# axiom_beta_plugin_module_3xPMOD_v1_2_r1_.net
KiCad netlist of a schematic drawn in EAGLE
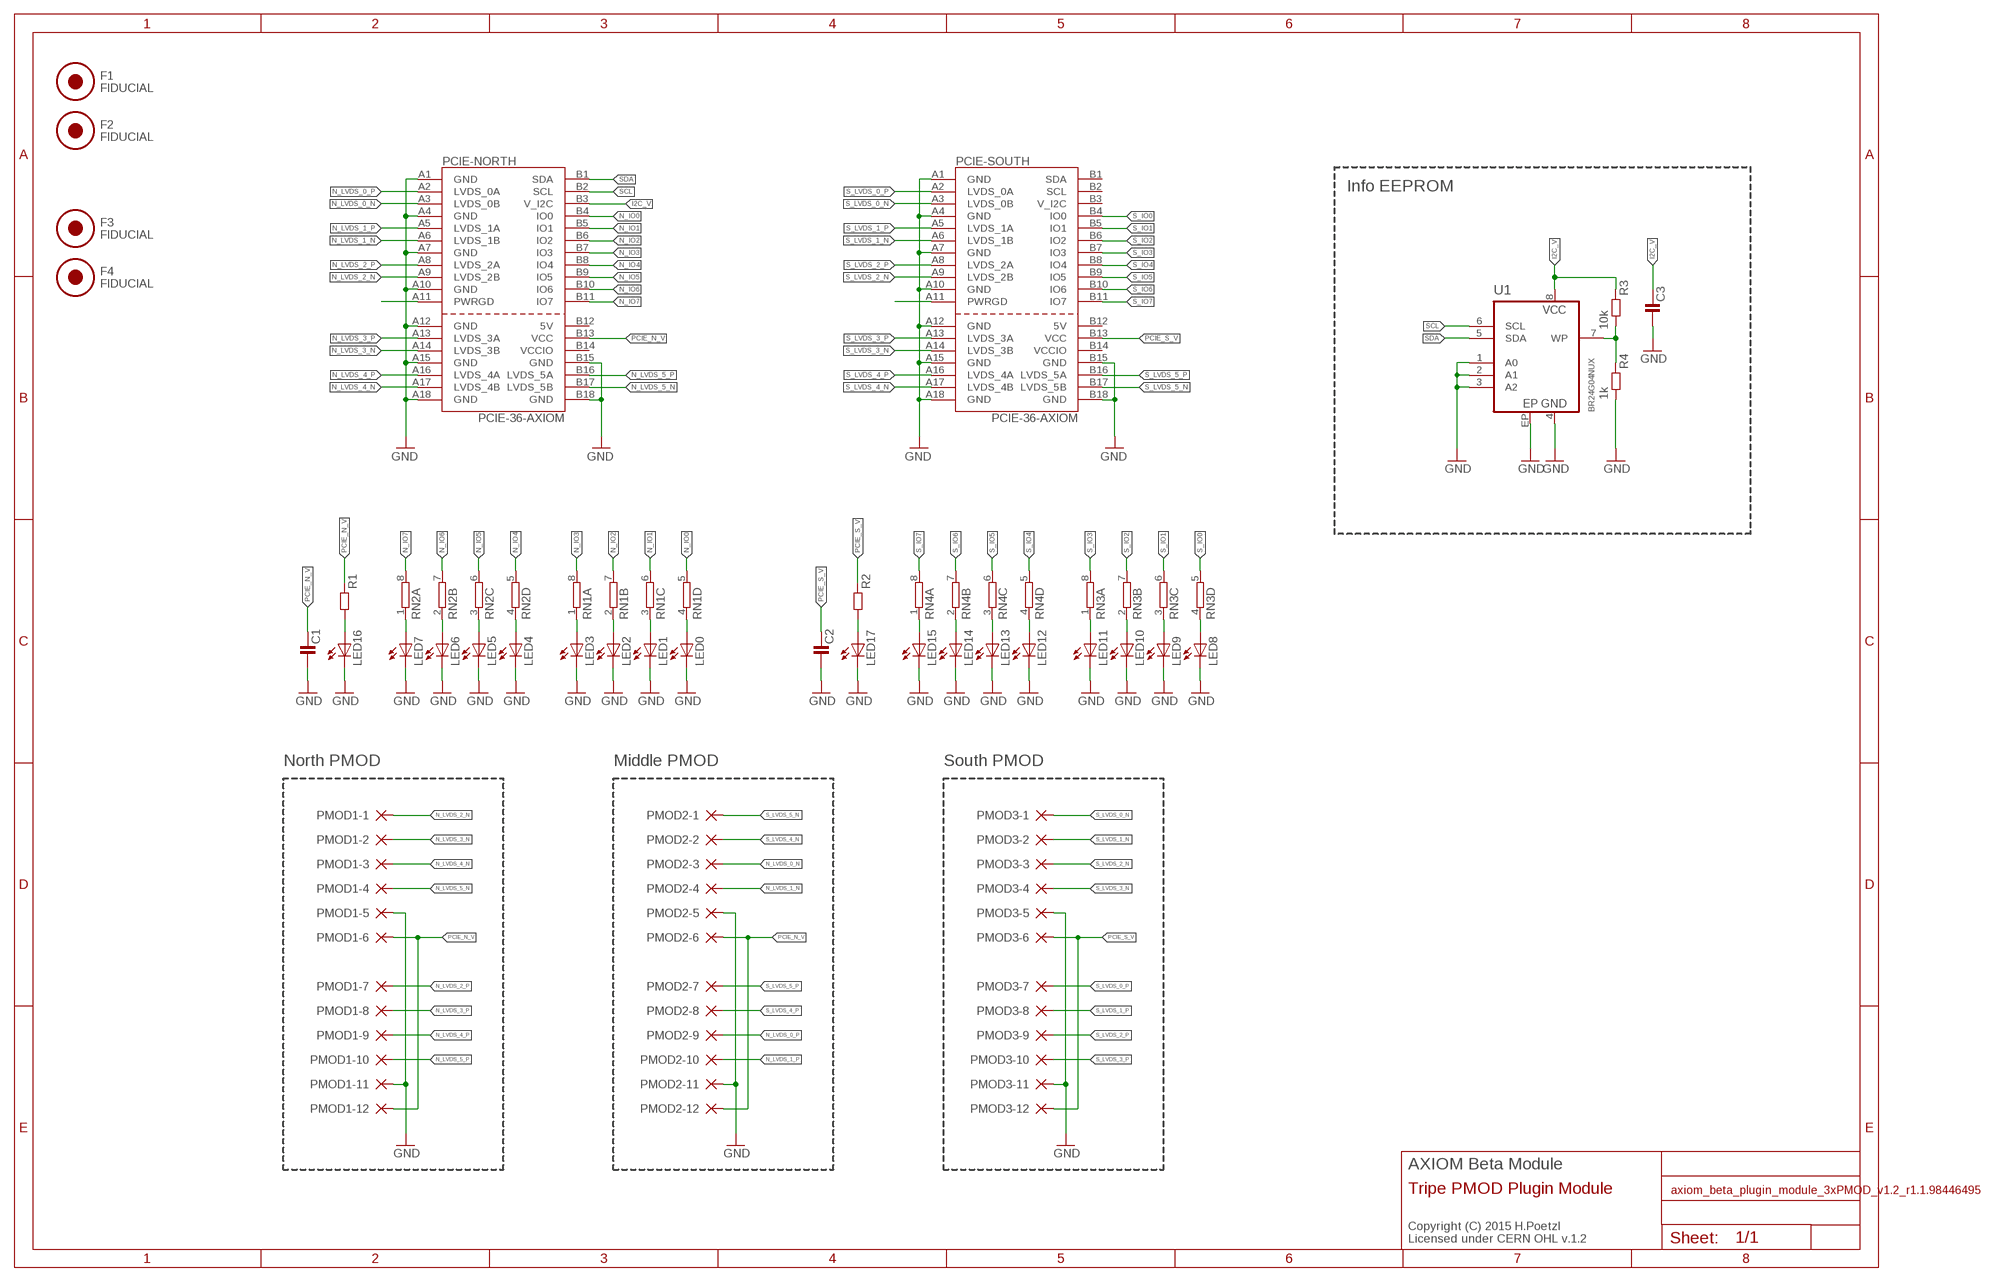
[diagram p0: schematic, sheet 1]

(export (version "E")
  (design (tool "Eeschema 10.0.6"))
  (components
    (comp (ref "C1")
      (value "C1206-A")
      (footprint "eagle-import:1206-A")
      (libsource (lib "eagle-import") (part "C1206-A"))
    )
    (comp (ref "C2")
      (value "C1206-A")
      (footprint "eagle-import:1206-A")
      (libsource (lib "eagle-import") (part "C1206-A"))
    )
    (comp (ref "C3")
      (value "C0402-B")
      (footprint "eagle-import:0402-B")
      (libsource (lib "eagle-import") (part "C0402-B"))
    )
    (comp (ref "F1")
      (value "FIDUCIAL")
      (footprint "eagle-import:FID_ARROW")
      (libsource (lib "eagle-import") (part "FIDUCIAL"))
    )
    (comp (ref "F2")
      (value "FIDUCIAL")
      (footprint "eagle-import:FID_ARROW")
      (libsource (lib "eagle-import") (part "FIDUCIAL"))
    )
    (comp (ref "F3")
      (value "FIDUCIAL")
      (footprint "eagle-import:FID_ARROW")
      (libsource (lib "eagle-import") (part "FIDUCIAL"))
    )
    (comp (ref "F4")
      (value "FIDUCIAL")
      (footprint "eagle-import:FID_ARROW")
      (libsource (lib "eagle-import") (part "FIDUCIAL"))
    )
    (comp (ref "LED0")
      (value "LEDCHIPLED_0603")
      (footprint "eagle-import:CHIPLED_0603")
      (libsource (lib "eagle-import") (part "LEDCHIPLED_0603"))
    )
    (comp (ref "LED1")
      (value "LEDCHIPLED_0603")
      (footprint "eagle-import:CHIPLED_0603")
      (libsource (lib "eagle-import") (part "LEDCHIPLED_0603"))
    )
    (comp (ref "LED2")
      (value "LEDCHIPLED_0603")
      (footprint "eagle-import:CHIPLED_0603")
      (libsource (lib "eagle-import") (part "LEDCHIPLED_0603"))
    )
    (comp (ref "LED3")
      (value "LEDCHIPLED_0603")
      (footprint "eagle-import:CHIPLED_0603")
      (libsource (lib "eagle-import") (part "LEDCHIPLED_0603"))
    )
    (comp (ref "LED4")
      (value "LEDCHIPLED_0603")
      (footprint "eagle-import:CHIPLED_0603")
      (libsource (lib "eagle-import") (part "LEDCHIPLED_0603"))
    )
    (comp (ref "LED5")
      (value "LEDCHIPLED_0603")
      (footprint "eagle-import:CHIPLED_0603")
      (libsource (lib "eagle-import") (part "LEDCHIPLED_0603"))
    )
    (comp (ref "LED6")
      (value "LEDCHIPLED_0603")
      (footprint "eagle-import:CHIPLED_0603")
      (libsource (lib "eagle-import") (part "LEDCHIPLED_0603"))
    )
    (comp (ref "LED7")
      (value "LEDCHIPLED_0603")
      (footprint "eagle-import:CHIPLED_0603")
      (libsource (lib "eagle-import") (part "LEDCHIPLED_0603"))
    )
    (comp (ref "LED8")
      (value "LEDCHIPLED_0603")
      (footprint "eagle-import:CHIPLED_0603")
      (libsource (lib "eagle-import") (part "LEDCHIPLED_0603"))
    )
    (comp (ref "LED9")
      (value "LEDCHIPLED_0603")
      (footprint "eagle-import:CHIPLED_0603")
      (libsource (lib "eagle-import") (part "LEDCHIPLED_0603"))
    )
    (comp (ref "LED10")
      (value "LEDCHIPLED_0603")
      (footprint "eagle-import:CHIPLED_0603")
      (libsource (lib "eagle-import") (part "LEDCHIPLED_0603"))
    )
    (comp (ref "LED11")
      (value "LEDCHIPLED_0603")
      (footprint "eagle-import:CHIPLED_0603")
      (libsource (lib "eagle-import") (part "LEDCHIPLED_0603"))
    )
    (comp (ref "LED12")
      (value "LEDCHIPLED_0603")
      (footprint "eagle-import:CHIPLED_0603")
      (libsource (lib "eagle-import") (part "LEDCHIPLED_0603"))
    )
    (comp (ref "LED13")
      (value "LEDCHIPLED_0603")
      (footprint "eagle-import:CHIPLED_0603")
      (libsource (lib "eagle-import") (part "LEDCHIPLED_0603"))
    )
    (comp (ref "LED14")
      (value "LEDCHIPLED_0603")
      (footprint "eagle-import:CHIPLED_0603")
      (libsource (lib "eagle-import") (part "LEDCHIPLED_0603"))
    )
    (comp (ref "LED15")
      (value "LEDCHIPLED_0603")
      (footprint "eagle-import:CHIPLED_0603")
      (libsource (lib "eagle-import") (part "LEDCHIPLED_0603"))
    )
    (comp (ref "LED16")
      (value "LEDCHIPLED_0603")
      (footprint "eagle-import:CHIPLED_0603")
      (libsource (lib "eagle-import") (part "LEDCHIPLED_0603"))
    )
    (comp (ref "LED17")
      (value "LEDCHIPLED_0603")
      (footprint "eagle-import:CHIPLED_0603")
      (libsource (lib "eagle-import") (part "LEDCHIPLED_0603"))
    )
    (comp (ref "PCIE-NORTH")
      (value "PCIE-36-AXIOM")
      (footprint "eagle-import:PCIE-36-AXIOM")
      (libsource (lib "eagle-import") (part "PCIE-36-AXIOM"))
    )
    (comp (ref "PCIE-SOUTH")
      (value "PCIE-36-AXIOM")
      (footprint "eagle-import:PCIE-36-AXIOM")
      (libsource (lib "eagle-import") (part "PCIE-36-AXIOM"))
    )
    (comp (ref "PMOD1-1")
      (value "SMD-PAD1.6X3.8MM-U")
      (footprint "eagle-import:1.6X3.8U-MM")
      (libsource (lib "eagle-import") (part "SMD-PAD1.6X3.8MM-U"))
    )
    (comp (ref "PMOD1-2")
      (value "SMD-PAD1.6X3.8MM-U")
      (footprint "eagle-import:1.6X3.8U-MM")
      (libsource (lib "eagle-import") (part "SMD-PAD1.6X3.8MM-U"))
    )
    (comp (ref "PMOD1-3")
      (value "SMD-PAD1.6X3.8MM-U")
      (footprint "eagle-import:1.6X3.8U-MM")
      (libsource (lib "eagle-import") (part "SMD-PAD1.6X3.8MM-U"))
    )
    (comp (ref "PMOD1-4")
      (value "SMD-PAD1.6X3.8MM-U")
      (footprint "eagle-import:1.6X3.8U-MM")
      (libsource (lib "eagle-import") (part "SMD-PAD1.6X3.8MM-U"))
    )
    (comp (ref "PMOD1-5")
      (value "SMD-PAD1.6X3.8MM-U")
      (footprint "eagle-import:1.6X3.8U-MM")
      (libsource (lib "eagle-import") (part "SMD-PAD1.6X3.8MM-U"))
    )
    (comp (ref "PMOD1-6")
      (value "SMD-PAD1.6X3.8MM-U")
      (footprint "eagle-import:1.6X3.8U-MM")
      (libsource (lib "eagle-import") (part "SMD-PAD1.6X3.8MM-U"))
    )
    (comp (ref "PMOD1-7")
      (value "SMD-PAD1.6X3.8MM-U")
      (footprint "eagle-import:1.6X3.8U-MM")
      (libsource (lib "eagle-import") (part "SMD-PAD1.6X3.8MM-U"))
    )
    (comp (ref "PMOD1-8")
      (value "SMD-PAD1.6X3.8MM-U")
      (footprint "eagle-import:1.6X3.8U-MM")
      (libsource (lib "eagle-import") (part "SMD-PAD1.6X3.8MM-U"))
    )
    (comp (ref "PMOD1-9")
      (value "SMD-PAD1.6X3.8MM-U")
      (footprint "eagle-import:1.6X3.8U-MM")
      (libsource (lib "eagle-import") (part "SMD-PAD1.6X3.8MM-U"))
    )
    (comp (ref "PMOD1-10")
      (value "SMD-PAD1.6X3.8MM-U")
      (footprint "eagle-import:1.6X3.8U-MM")
      (libsource (lib "eagle-import") (part "SMD-PAD1.6X3.8MM-U"))
    )
    (comp (ref "PMOD1-11")
      (value "SMD-PAD1.6X3.8MM-U")
      (footprint "eagle-import:1.6X3.8U-MM")
      (libsource (lib "eagle-import") (part "SMD-PAD1.6X3.8MM-U"))
    )
    (comp (ref "PMOD1-12")
      (value "SMD-PAD1.6X3.8MM-U")
      (footprint "eagle-import:1.6X3.8U-MM")
      (libsource (lib "eagle-import") (part "SMD-PAD1.6X3.8MM-U"))
    )
    (comp (ref "PMOD2-1")
      (value "SMD-PAD1.6X3.8MM-U")
      (footprint "eagle-import:1.6X3.8U-MM")
      (libsource (lib "eagle-import") (part "SMD-PAD1.6X3.8MM-U"))
    )
    (comp (ref "PMOD2-2")
      (value "SMD-PAD1.6X3.8MM-U")
      (footprint "eagle-import:1.6X3.8U-MM")
      (libsource (lib "eagle-import") (part "SMD-PAD1.6X3.8MM-U"))
    )
    (comp (ref "PMOD2-3")
      (value "SMD-PAD1.6X3.8MM-U")
      (footprint "eagle-import:1.6X3.8U-MM")
      (libsource (lib "eagle-import") (part "SMD-PAD1.6X3.8MM-U"))
    )
    (comp (ref "PMOD2-4")
      (value "SMD-PAD1.6X3.8MM-U")
      (footprint "eagle-import:1.6X3.8U-MM")
      (libsource (lib "eagle-import") (part "SMD-PAD1.6X3.8MM-U"))
    )
    (comp (ref "PMOD2-5")
      (value "SMD-PAD1.6X3.8MM-U")
      (footprint "eagle-import:1.6X3.8U-MM")
      (libsource (lib "eagle-import") (part "SMD-PAD1.6X3.8MM-U"))
    )
    (comp (ref "PMOD2-6")
      (value "SMD-PAD1.6X3.8MM-U")
      (footprint "eagle-import:1.6X3.8U-MM")
      (libsource (lib "eagle-import") (part "SMD-PAD1.6X3.8MM-U"))
    )
    (comp (ref "PMOD2-7")
      (value "SMD-PAD1.6X3.8MM-U")
      (footprint "eagle-import:1.6X3.8U-MM")
      (libsource (lib "eagle-import") (part "SMD-PAD1.6X3.8MM-U"))
    )
    (comp (ref "PMOD2-8")
      (value "SMD-PAD1.6X3.8MM-U")
      (footprint "eagle-import:1.6X3.8U-MM")
      (libsource (lib "eagle-import") (part "SMD-PAD1.6X3.8MM-U"))
    )
    (comp (ref "PMOD2-9")
      (value "SMD-PAD1.6X3.8MM-U")
      (footprint "eagle-import:1.6X3.8U-MM")
      (libsource (lib "eagle-import") (part "SMD-PAD1.6X3.8MM-U"))
    )
    (comp (ref "PMOD2-10")
      (value "SMD-PAD1.6X3.8MM-U")
      (footprint "eagle-import:1.6X3.8U-MM")
      (libsource (lib "eagle-import") (part "SMD-PAD1.6X3.8MM-U"))
    )
    (comp (ref "PMOD2-11")
      (value "SMD-PAD1.6X3.8MM-U")
      (footprint "eagle-import:1.6X3.8U-MM")
      (libsource (lib "eagle-import") (part "SMD-PAD1.6X3.8MM-U"))
    )
    (comp (ref "PMOD2-12")
      (value "SMD-PAD1.6X3.8MM-U")
      (footprint "eagle-import:1.6X3.8U-MM")
      (libsource (lib "eagle-import") (part "SMD-PAD1.6X3.8MM-U"))
    )
    (comp (ref "PMOD3-1")
      (value "SMD-PAD1.6X3.8MM-U")
      (footprint "eagle-import:1.6X3.8U-MM")
      (libsource (lib "eagle-import") (part "SMD-PAD1.6X3.8MM-U"))
    )
    (comp (ref "PMOD3-2")
      (value "SMD-PAD1.6X3.8MM-U")
      (footprint "eagle-import:1.6X3.8U-MM")
      (libsource (lib "eagle-import") (part "SMD-PAD1.6X3.8MM-U"))
    )
    (comp (ref "PMOD3-3")
      (value "SMD-PAD1.6X3.8MM-U")
      (footprint "eagle-import:1.6X3.8U-MM")
      (libsource (lib "eagle-import") (part "SMD-PAD1.6X3.8MM-U"))
    )
    (comp (ref "PMOD3-4")
      (value "SMD-PAD1.6X3.8MM-U")
      (footprint "eagle-import:1.6X3.8U-MM")
      (libsource (lib "eagle-import") (part "SMD-PAD1.6X3.8MM-U"))
    )
    (comp (ref "PMOD3-5")
      (value "SMD-PAD1.6X3.8MM-U")
      (footprint "eagle-import:1.6X3.8U-MM")
      (libsource (lib "eagle-import") (part "SMD-PAD1.6X3.8MM-U"))
    )
    (comp (ref "PMOD3-6")
      (value "SMD-PAD1.6X3.8MM-U")
      (footprint "eagle-import:1.6X3.8U-MM")
      (libsource (lib "eagle-import") (part "SMD-PAD1.6X3.8MM-U"))
    )
    (comp (ref "PMOD3-7")
      (value "SMD-PAD1.6X3.8MM-U")
      (footprint "eagle-import:1.6X3.8U-MM")
      (libsource (lib "eagle-import") (part "SMD-PAD1.6X3.8MM-U"))
    )
    (comp (ref "PMOD3-8")
      (value "SMD-PAD1.6X3.8MM-U")
      (footprint "eagle-import:1.6X3.8U-MM")
      (libsource (lib "eagle-import") (part "SMD-PAD1.6X3.8MM-U"))
    )
    (comp (ref "PMOD3-9")
      (value "SMD-PAD1.6X3.8MM-U")
      (footprint "eagle-import:1.6X3.8U-MM")
      (libsource (lib "eagle-import") (part "SMD-PAD1.6X3.8MM-U"))
    )
    (comp (ref "PMOD3-10")
      (value "SMD-PAD1.6X3.8MM-U")
      (footprint "eagle-import:1.6X3.8U-MM")
      (libsource (lib "eagle-import") (part "SMD-PAD1.6X3.8MM-U"))
    )
    (comp (ref "PMOD3-11")
      (value "SMD-PAD1.6X3.8MM-U")
      (footprint "eagle-import:1.6X3.8U-MM")
      (libsource (lib "eagle-import") (part "SMD-PAD1.6X3.8MM-U"))
    )
    (comp (ref "PMOD3-12")
      (value "SMD-PAD1.6X3.8MM-U")
      (footprint "eagle-import:1.6X3.8U-MM")
      (libsource (lib "eagle-import") (part "SMD-PAD1.6X3.8MM-U"))
    )
    (comp (ref "R1")
      (value "R0402-B")
      (footprint "eagle-import:0402-B")
      (libsource (lib "eagle-import") (part "R0402-B"))
    )
    (comp (ref "R2")
      (value "R0402-B")
      (footprint "eagle-import:0402-B")
      (libsource (lib "eagle-import") (part "R0402-B"))
    )
    (comp (ref "R3")
      (value "10k")
      (footprint "eagle-import:0402-B")
      (libsource (lib "eagle-import") (part "R0402-B"))
    )
    (comp (ref "R4")
      (value "1k")
      (footprint "eagle-import:0402-B")
      (libsource (lib "eagle-import") (part "R0402-B"))
    )
    (comp (ref "RN1")
      (value "4R-NCAY16")
      (footprint "eagle-import:CAY16")
      (libsource (lib "eagle-import") (part "4R-NCAY16"))
    )
    (comp (ref "RN2")
      (value "4R-NCAY16")
      (footprint "eagle-import:CAY16")
      (libsource (lib "eagle-import") (part "4R-NCAY16"))
    )
    (comp (ref "RN3")
      (value "4R-NCAY16")
      (footprint "eagle-import:CAY16")
      (libsource (lib "eagle-import") (part "4R-NCAY16"))
    )
    (comp (ref "RN4")
      (value "4R-NCAY16")
      (footprint "eagle-import:CAY16")
      (libsource (lib "eagle-import") (part "4R-NCAY16"))
    )
    (comp (ref "U1")
      (value "BR24G04NUX")
      (footprint "eagle-import:DFN200X300X100-9N")
      (libsource (lib "eagle-import") (part "BR24G04NUX"))
    )
  )
  (nets
    (net (code "1") (name "GND") (class "Default")
      (node (ref "C1") (pin "2") (pinfunction "2_2") (pintype "passive"))
      (node (ref "C2") (pin "2") (pinfunction "2_2") (pintype "passive"))
      (node (ref "C3") (pin "2") (pinfunction "2_2") (pintype "passive"))
      (node (ref "LED0") (pin "C") (pinfunction "C_C") (pintype "passive"))
      (node (ref "LED1") (pin "C") (pinfunction "C_C") (pintype "passive"))
      (node (ref "LED10") (pin "C") (pinfunction "C_C") (pintype "passive"))
      (node (ref "LED11") (pin "C") (pinfunction "C_C") (pintype "passive"))
      (node (ref "LED12") (pin "C") (pinfunction "C_C") (pintype "passive"))
      (node (ref "LED13") (pin "C") (pinfunction "C_C") (pintype "passive"))
      (node (ref "LED14") (pin "C") (pinfunction "C_C") (pintype "passive"))
      (node (ref "LED15") (pin "C") (pinfunction "C_C") (pintype "passive"))
      (node (ref "LED16") (pin "C") (pinfunction "C_C") (pintype "passive"))
      (node (ref "LED17") (pin "C") (pinfunction "C_C") (pintype "passive"))
      (node (ref "LED2") (pin "C") (pinfunction "C_C") (pintype "passive"))
      (node (ref "LED3") (pin "C") (pinfunction "C_C") (pintype "passive"))
      (node (ref "LED4") (pin "C") (pinfunction "C_C") (pintype "passive"))
      (node (ref "LED5") (pin "C") (pinfunction "C_C") (pintype "passive"))
      (node (ref "LED6") (pin "C") (pinfunction "C_C") (pintype "passive"))
      (node (ref "LED7") (pin "C") (pinfunction "C_C") (pintype "passive"))
      (node (ref "LED8") (pin "C") (pinfunction "C_C") (pintype "passive"))
      (node (ref "LED9") (pin "C") (pinfunction "C_C") (pintype "passive"))
      (node (ref "PCIE-NORTH") (pin "A1") (pinfunction "GND_A1") (pintype "passive"))
      (node (ref "PCIE-NORTH") (pin "A10") (pinfunction "GND_A10") (pintype "passive"))
      (node (ref "PCIE-NORTH") (pin "A12") (pinfunction "GND_A12") (pintype "passive"))
      (node (ref "PCIE-NORTH") (pin "A15") (pinfunction "GND_A15") (pintype "passive"))
      (node (ref "PCIE-NORTH") (pin "A18") (pinfunction "GND_A18") (pintype "passive"))
      (node (ref "PCIE-NORTH") (pin "A4") (pinfunction "GND_A4") (pintype "passive"))
      (node (ref "PCIE-NORTH") (pin "A7") (pinfunction "GND_A7") (pintype "passive"))
      (node (ref "PCIE-NORTH") (pin "B15") (pinfunction "GND_B15") (pintype "passive"))
      (node (ref "PCIE-NORTH") (pin "B18") (pinfunction "GND_B18") (pintype "passive"))
      (node (ref "PCIE-SOUTH") (pin "A1") (pinfunction "GND_A1") (pintype "passive"))
      (node (ref "PCIE-SOUTH") (pin "A10") (pinfunction "GND_A10") (pintype "passive"))
      (node (ref "PCIE-SOUTH") (pin "A12") (pinfunction "GND_A12") (pintype "passive"))
      (node (ref "PCIE-SOUTH") (pin "A15") (pinfunction "GND_A15") (pintype "passive"))
      (node (ref "PCIE-SOUTH") (pin "A18") (pinfunction "GND_A18") (pintype "passive"))
      (node (ref "PCIE-SOUTH") (pin "A4") (pinfunction "GND_A4") (pintype "passive"))
      (node (ref "PCIE-SOUTH") (pin "A7") (pinfunction "GND_A7") (pintype "passive"))
      (node (ref "PCIE-SOUTH") (pin "B15") (pinfunction "GND_B15") (pintype "passive"))
      (node (ref "PCIE-SOUTH") (pin "B18") (pinfunction "GND_B18") (pintype "passive"))
      (node (ref "PMOD1-11") (pin "1") (pinfunction "P_1") (pintype "passive"))
      (node (ref "PMOD1-5") (pin "1") (pinfunction "P_1") (pintype "passive"))
      (node (ref "PMOD2-11") (pin "1") (pinfunction "P_1") (pintype "passive"))
      (node (ref "PMOD2-5") (pin "1") (pinfunction "P_1") (pintype "passive"))
      (node (ref "PMOD3-11") (pin "1") (pinfunction "P_1") (pintype "passive"))
      (node (ref "PMOD3-5") (pin "1") (pinfunction "P_1") (pintype "passive"))
      (node (ref "R4") (pin "2") (pinfunction "2_2") (pintype "passive"))
      (node (ref "U1") (pin "1") (pinfunction "A0_1") (pintype "input"))
      (node (ref "U1") (pin "2") (pinfunction "A1_2") (pintype "input"))
      (node (ref "U1") (pin "3") (pinfunction "A2_3") (pintype "input"))
      (node (ref "U1") (pin "4") (pinfunction "GND_4") (pintype "passive"))
      (node (ref "U1") (pin "EP") (pinfunction "EP_EP") (pintype "passive"))
    )
    (net (code "2") (name "I2C_V") (class "Default")
      (node (ref "C3") (pin "1") (pinfunction "1_1") (pintype "passive"))
      (node (ref "PCIE-NORTH") (pin "B3") (pinfunction "V_I2C_B3") (pintype "passive"))
      (node (ref "R3") (pin "1") (pinfunction "1_1") (pintype "passive"))
      (node (ref "U1") (pin "8") (pinfunction "VCC_8") (pintype "power_in"))
    )
    (net (code "3") (name "N_IO0") (class "Default")
      (node (ref "PCIE-NORTH") (pin "B4") (pinfunction "IO0_B4") (pintype "passive"))
      (node (ref "RN1") (pin "5") (pinfunction "2_5") (pintype "passive"))
    )
    (net (code "4") (name "N_IO1") (class "Default")
      (node (ref "PCIE-NORTH") (pin "B5") (pinfunction "IO1_B5") (pintype "passive"))
      (node (ref "RN1") (pin "6") (pinfunction "2_6") (pintype "passive"))
    )
    (net (code "5") (name "N_IO2") (class "Default")
      (node (ref "PCIE-NORTH") (pin "B6") (pinfunction "IO2_B6") (pintype "passive"))
      (node (ref "RN1") (pin "7") (pinfunction "2_7") (pintype "passive"))
    )
    (net (code "6") (name "N_IO3") (class "Default")
      (node (ref "PCIE-NORTH") (pin "B7") (pinfunction "IO3_B7") (pintype "passive"))
      (node (ref "RN1") (pin "8") (pinfunction "2_8") (pintype "passive"))
    )
    (net (code "7") (name "N_IO4") (class "Default")
      (node (ref "PCIE-NORTH") (pin "B8") (pinfunction "IO4_B8") (pintype "passive"))
      (node (ref "RN2") (pin "5") (pinfunction "2_5") (pintype "passive"))
    )
    (net (code "8") (name "N_IO5") (class "Default")
      (node (ref "PCIE-NORTH") (pin "B9") (pinfunction "IO5_B9") (pintype "passive"))
      (node (ref "RN2") (pin "6") (pinfunction "2_6") (pintype "passive"))
    )
    (net (code "9") (name "N_IO6") (class "Default")
      (node (ref "PCIE-NORTH") (pin "B10") (pinfunction "IO6_B10") (pintype "passive"))
      (node (ref "RN2") (pin "7") (pinfunction "2_7") (pintype "passive"))
    )
    (net (code "10") (name "N_IO7") (class "Default")
      (node (ref "PCIE-NORTH") (pin "B11") (pinfunction "IO7_B11") (pintype "passive"))
      (node (ref "RN2") (pin "8") (pinfunction "2_8") (pintype "passive"))
    )
    (net (code "11") (name "N_LVDS_0_N") (class "Default")
      (node (ref "PCIE-NORTH") (pin "A3") (pinfunction "LVDS_0B_A3") (pintype "passive"))
      (node (ref "PMOD2-3") (pin "1") (pinfunction "P_1") (pintype "passive"))
    )
    (net (code "12") (name "N_LVDS_0_P") (class "Default")
      (node (ref "PCIE-NORTH") (pin "A2") (pinfunction "LVDS_0A_A2") (pintype "passive"))
      (node (ref "PMOD2-9") (pin "1") (pinfunction "P_1") (pintype "passive"))
    )
    (net (code "13") (name "N_LVDS_1_N") (class "Default")
      (node (ref "PCIE-NORTH") (pin "A6") (pinfunction "LVDS_1B_A6") (pintype "passive"))
      (node (ref "PMOD2-4") (pin "1") (pinfunction "P_1") (pintype "passive"))
    )
    (net (code "14") (name "N_LVDS_1_P") (class "Default")
      (node (ref "PCIE-NORTH") (pin "A5") (pinfunction "LVDS_1A_A5") (pintype "passive"))
      (node (ref "PMOD2-10") (pin "1") (pinfunction "P_1") (pintype "passive"))
    )
    (net (code "15") (name "N_LVDS_2_N") (class "Default")
      (node (ref "PCIE-NORTH") (pin "A9") (pinfunction "LVDS_2B_A9") (pintype "passive"))
      (node (ref "PMOD1-1") (pin "1") (pinfunction "P_1") (pintype "passive"))
    )
    (net (code "16") (name "N_LVDS_2_P") (class "Default")
      (node (ref "PCIE-NORTH") (pin "A8") (pinfunction "LVDS_2A_A8") (pintype "passive"))
      (node (ref "PMOD1-7") (pin "1") (pinfunction "P_1") (pintype "passive"))
    )
    (net (code "17") (name "N_LVDS_3_N") (class "Default")
      (node (ref "PCIE-NORTH") (pin "A14") (pinfunction "LVDS_3B_A14") (pintype "passive"))
      (node (ref "PMOD1-2") (pin "1") (pinfunction "P_1") (pintype "passive"))
    )
    (net (code "18") (name "N_LVDS_3_P") (class "Default")
      (node (ref "PCIE-NORTH") (pin "A13") (pinfunction "LVDS_3A_A13") (pintype "passive"))
      (node (ref "PMOD1-8") (pin "1") (pinfunction "P_1") (pintype "passive"))
    )
    (net (code "19") (name "N_LVDS_4_N") (class "Default")
      (node (ref "PCIE-NORTH") (pin "A17") (pinfunction "LVDS_4B_A17") (pintype "passive"))
      (node (ref "PMOD1-3") (pin "1") (pinfunction "P_1") (pintype "passive"))
    )
    (net (code "20") (name "N_LVDS_4_P") (class "Default")
      (node (ref "PCIE-NORTH") (pin "A16") (pinfunction "LVDS_4A_A16") (pintype "passive"))
      (node (ref "PMOD1-9") (pin "1") (pinfunction "P_1") (pintype "passive"))
    )
    (net (code "21") (name "N_LVDS_5_N") (class "Default")
      (node (ref "PCIE-NORTH") (pin "B17") (pinfunction "LVDS_5B_B17") (pintype "passive"))
      (node (ref "PMOD1-4") (pin "1") (pinfunction "P_1") (pintype "passive"))
    )
    (net (code "22") (name "N_LVDS_5_P") (class "Default")
      (node (ref "PCIE-NORTH") (pin "B16") (pinfunction "LVDS_5A_B16") (pintype "passive"))
      (node (ref "PMOD1-10") (pin "1") (pinfunction "P_1") (pintype "passive"))
    )
    (net (code "23") (name "Net-(LED3-PadA)") (class "Default")
      (node (ref "LED3") (pin "A") (pinfunction "A_A") (pintype "passive"))
      (node (ref "RN1") (pin "1") (pinfunction "1_1") (pintype "passive"))
    )
    (net (code "24") (name "Net-(LED7-PadA)") (class "Default")
      (node (ref "LED7") (pin "A") (pinfunction "A_A") (pintype "passive"))
      (node (ref "RN2") (pin "1") (pinfunction "1_1") (pintype "passive"))
    )
    (net (code "25") (name "Net-(LED11-PadA)") (class "Default")
      (node (ref "LED11") (pin "A") (pinfunction "A_A") (pintype "passive"))
      (node (ref "RN3") (pin "1") (pinfunction "1_1") (pintype "passive"))
    )
    (net (code "26") (name "Net-(LED15-PadA)") (class "Default")
      (node (ref "LED15") (pin "A") (pinfunction "A_A") (pintype "passive"))
      (node (ref "RN4") (pin "1") (pinfunction "1_1") (pintype "passive"))
    )
    (net (code "27") (name "Net-(LED16-PadA)") (class "Default")
      (node (ref "LED16") (pin "A") (pinfunction "A_A") (pintype "passive"))
      (node (ref "R1") (pin "2") (pinfunction "2_2") (pintype "passive"))
    )
    (net (code "28") (name "Net-(LED17-PadA)") (class "Default")
      (node (ref "LED17") (pin "A") (pinfunction "A_A") (pintype "passive"))
      (node (ref "R2") (pin "2") (pinfunction "2_2") (pintype "passive"))
    )
    (net (code "29") (name "Net-(RN1B-1)") (class "Default")
      (node (ref "LED2") (pin "A") (pinfunction "A_A") (pintype "passive"))
      (node (ref "RN1") (pin "2") (pinfunction "1_2") (pintype "passive"))
    )
    (net (code "30") (name "Net-(RN1C-1)") (class "Default")
      (node (ref "LED1") (pin "A") (pinfunction "A_A") (pintype "passive"))
      (node (ref "RN1") (pin "3") (pinfunction "1_3") (pintype "passive"))
    )
    (net (code "31") (name "Net-(RN1D-1)") (class "Default")
      (node (ref "LED0") (pin "A") (pinfunction "A_A") (pintype "passive"))
      (node (ref "RN1") (pin "4") (pinfunction "1_4") (pintype "passive"))
    )
    (net (code "32") (name "Net-(RN2B-1)") (class "Default")
      (node (ref "LED6") (pin "A") (pinfunction "A_A") (pintype "passive"))
      (node (ref "RN2") (pin "2") (pinfunction "1_2") (pintype "passive"))
    )
    (net (code "33") (name "Net-(RN2C-1)") (class "Default")
      (node (ref "LED5") (pin "A") (pinfunction "A_A") (pintype "passive"))
      (node (ref "RN2") (pin "3") (pinfunction "1_3") (pintype "passive"))
    )
    (net (code "34") (name "Net-(RN2D-1)") (class "Default")
      (node (ref "LED4") (pin "A") (pinfunction "A_A") (pintype "passive"))
      (node (ref "RN2") (pin "4") (pinfunction "1_4") (pintype "passive"))
    )
    (net (code "35") (name "Net-(RN3B-1)") (class "Default")
      (node (ref "LED10") (pin "A") (pinfunction "A_A") (pintype "passive"))
      (node (ref "RN3") (pin "2") (pinfunction "1_2") (pintype "passive"))
    )
    (net (code "36") (name "Net-(RN3C-1)") (class "Default")
      (node (ref "LED9") (pin "A") (pinfunction "A_A") (pintype "passive"))
      (node (ref "RN3") (pin "3") (pinfunction "1_3") (pintype "passive"))
    )
    (net (code "37") (name "Net-(RN3D-1)") (class "Default")
      (node (ref "LED8") (pin "A") (pinfunction "A_A") (pintype "passive"))
      (node (ref "RN3") (pin "4") (pinfunction "1_4") (pintype "passive"))
    )
    (net (code "38") (name "Net-(RN4B-1)") (class "Default")
      (node (ref "LED14") (pin "A") (pinfunction "A_A") (pintype "passive"))
      (node (ref "RN4") (pin "2") (pinfunction "1_2") (pintype "passive"))
    )
    (net (code "39") (name "Net-(RN4C-1)") (class "Default")
      (node (ref "LED13") (pin "A") (pinfunction "A_A") (pintype "passive"))
      (node (ref "RN4") (pin "3") (pinfunction "1_3") (pintype "passive"))
    )
    (net (code "40") (name "Net-(RN4D-1)") (class "Default")
      (node (ref "LED12") (pin "A") (pinfunction "A_A") (pintype "passive"))
      (node (ref "RN4") (pin "4") (pinfunction "1_4") (pintype "passive"))
    )
    (net (code "41") (name "Net-(U1-WP)") (class "Default")
      (node (ref "R3") (pin "2") (pinfunction "2_2") (pintype "passive"))
      (node (ref "R4") (pin "1") (pinfunction "1_1") (pintype "passive"))
      (node (ref "U1") (pin "7") (pinfunction "WP_7") (pintype "input"))
    )
    (net (code "42") (name "PCIE_N_V") (class "Default")
      (node (ref "C1") (pin "1") (pinfunction "1_1") (pintype "passive"))
      (node (ref "PCIE-NORTH") (pin "B13") (pinfunction "VCC_B13") (pintype "passive"))
      (node (ref "PMOD1-12") (pin "1") (pinfunction "P_1") (pintype "passive"))
      (node (ref "PMOD1-6") (pin "1") (pinfunction "P_1") (pintype "passive"))
      (node (ref "PMOD2-12") (pin "1") (pinfunction "P_1") (pintype "passive"))
      (node (ref "PMOD2-6") (pin "1") (pinfunction "P_1") (pintype "passive"))
      (node (ref "R1") (pin "1") (pinfunction "1_1") (pintype "passive"))
    )
    (net (code "43") (name "PCIE_S_V") (class "Default")
      (node (ref "C2") (pin "1") (pinfunction "1_1") (pintype "passive"))
      (node (ref "PCIE-SOUTH") (pin "B13") (pinfunction "VCC_B13") (pintype "passive"))
      (node (ref "PMOD3-12") (pin "1") (pinfunction "P_1") (pintype "passive"))
      (node (ref "PMOD3-6") (pin "1") (pinfunction "P_1") (pintype "passive"))
      (node (ref "R2") (pin "1") (pinfunction "1_1") (pintype "passive"))
    )
    (net (code "44") (name "SCL") (class "Default")
      (node (ref "PCIE-NORTH") (pin "B2") (pinfunction "SCL_B2") (pintype "passive"))
      (node (ref "U1") (pin "6") (pinfunction "SCL_6") (pintype "input"))
    )
    (net (code "45") (name "SDA") (class "Default")
      (node (ref "PCIE-NORTH") (pin "B1") (pinfunction "SDA_B1") (pintype "passive"))
      (node (ref "U1") (pin "5") (pinfunction "SDA_5") (pintype "bidirectional"))
    )
    (net (code "46") (name "S_IO0") (class "Default")
      (node (ref "PCIE-SOUTH") (pin "B4") (pinfunction "IO0_B4") (pintype "passive"))
      (node (ref "RN3") (pin "5") (pinfunction "2_5") (pintype "passive"))
    )
    (net (code "47") (name "S_IO1") (class "Default")
      (node (ref "PCIE-SOUTH") (pin "B5") (pinfunction "IO1_B5") (pintype "passive"))
      (node (ref "RN3") (pin "6") (pinfunction "2_6") (pintype "passive"))
    )
    (net (code "48") (name "S_IO2") (class "Default")
      (node (ref "PCIE-SOUTH") (pin "B6") (pinfunction "IO2_B6") (pintype "passive"))
      (node (ref "RN3") (pin "7") (pinfunction "2_7") (pintype "passive"))
    )
    (net (code "49") (name "S_IO3") (class "Default")
      (node (ref "PCIE-SOUTH") (pin "B7") (pinfunction "IO3_B7") (pintype "passive"))
      (node (ref "RN3") (pin "8") (pinfunction "2_8") (pintype "passive"))
    )
    (net (code "50") (name "S_IO4") (class "Default")
      (node (ref "PCIE-SOUTH") (pin "B8") (pinfunction "IO4_B8") (pintype "passive"))
      (node (ref "RN4") (pin "5") (pinfunction "2_5") (pintype "passive"))
    )
    (net (code "51") (name "S_IO5") (class "Default")
      (node (ref "PCIE-SOUTH") (pin "B9") (pinfunction "IO5_B9") (pintype "passive"))
      (node (ref "RN4") (pin "6") (pinfunction "2_6") (pintype "passive"))
    )
    (net (code "52") (name "S_IO6") (class "Default")
      (node (ref "PCIE-SOUTH") (pin "B10") (pinfunction "IO6_B10") (pintype "passive"))
      (node (ref "RN4") (pin "7") (pinfunction "2_7") (pintype "passive"))
    )
    (net (code "53") (name "S_IO7") (class "Default")
      (node (ref "PCIE-SOUTH") (pin "B11") (pinfunction "IO7_B11") (pintype "passive"))
      (node (ref "RN4") (pin "8") (pinfunction "2_8") (pintype "passive"))
    )
    (net (code "54") (name "S_LVDS_0_N") (class "Default")
      (node (ref "PCIE-SOUTH") (pin "A3") (pinfunction "LVDS_0B_A3") (pintype "passive"))
      (node (ref "PMOD3-1") (pin "1") (pinfunction "P_1") (pintype "passive"))
    )
    (net (code "55") (name "S_LVDS_0_P") (class "Default")
      (node (ref "PCIE-SOUTH") (pin "A2") (pinfunction "LVDS_0A_A2") (pintype "passive"))
      (node (ref "PMOD3-7") (pin "1") (pinfunction "P_1") (pintype "passive"))
    )
    (net (code "56") (name "S_LVDS_1_N") (class "Default")
      (node (ref "PCIE-SOUTH") (pin "A6") (pinfunction "LVDS_1B_A6") (pintype "passive"))
      (node (ref "PMOD3-2") (pin "1") (pinfunction "P_1") (pintype "passive"))
    )
    (net (code "57") (name "S_LVDS_1_P") (class "Default")
      (node (ref "PCIE-SOUTH") (pin "A5") (pinfunction "LVDS_1A_A5") (pintype "passive"))
      (node (ref "PMOD3-8") (pin "1") (pinfunction "P_1") (pintype "passive"))
    )
    (net (code "58") (name "S_LVDS_2_N") (class "Default")
      (node (ref "PCIE-SOUTH") (pin "A9") (pinfunction "LVDS_2B_A9") (pintype "passive"))
      (node (ref "PMOD3-3") (pin "1") (pinfunction "P_1") (pintype "passive"))
    )
    (net (code "59") (name "S_LVDS_2_P") (class "Default")
      (node (ref "PCIE-SOUTH") (pin "A8") (pinfunction "LVDS_2A_A8") (pintype "passive"))
      (node (ref "PMOD3-9") (pin "1") (pinfunction "P_1") (pintype "passive"))
    )
    (net (code "60") (name "S_LVDS_3_N") (class "Default")
      (node (ref "PCIE-SOUTH") (pin "A14") (pinfunction "LVDS_3B_A14") (pintype "passive"))
      (node (ref "PMOD3-4") (pin "1") (pinfunction "P_1") (pintype "passive"))
    )
    (net (code "61") (name "S_LVDS_3_P") (class "Default")
      (node (ref "PCIE-SOUTH") (pin "A13") (pinfunction "LVDS_3A_A13") (pintype "passive"))
      (node (ref "PMOD3-10") (pin "1") (pinfunction "P_1") (pintype "passive"))
    )
    (net (code "62") (name "S_LVDS_4_N") (class "Default")
      (node (ref "PCIE-SOUTH") (pin "A17") (pinfunction "LVDS_4B_A17") (pintype "passive"))
      (node (ref "PMOD2-2") (pin "1") (pinfunction "P_1") (pintype "passive"))
    )
    (net (code "63") (name "S_LVDS_4_P") (class "Default")
      (node (ref "PCIE-SOUTH") (pin "A16") (pinfunction "LVDS_4A_A16") (pintype "passive"))
      (node (ref "PMOD2-8") (pin "1") (pinfunction "P_1") (pintype "passive"))
    )
    (net (code "64") (name "S_LVDS_5_N") (class "Default")
      (node (ref "PCIE-SOUTH") (pin "B17") (pinfunction "LVDS_5B_B17") (pintype "passive"))
      (node (ref "PMOD2-1") (pin "1") (pinfunction "P_1") (pintype "passive"))
    )
    (net (code "65") (name "S_LVDS_5_P") (class "Default")
      (node (ref "PCIE-SOUTH") (pin "B16") (pinfunction "LVDS_5A_B16") (pintype "passive"))
      (node (ref "PMOD2-7") (pin "1") (pinfunction "P_1") (pintype "passive"))
    )
    (net (code "66") (name "unconnected-(PCIE-NORTH-5V-PadB12)") (class "Default")
      (node (ref "PCIE-NORTH") (pin "B12") (pinfunction "5V_B12") (pintype "passive"))
    )
    (net (code "67") (name "unconnected-(PCIE-NORTH-PWRGD-PadA11)") (class "Default")
      (node (ref "PCIE-NORTH") (pin "A11") (pinfunction "PWRGD_A11") (pintype "passive"))
    )
    (net (code "68") (name "unconnected-(PCIE-NORTH-VCCIO-PadB14)") (class "Default")
      (node (ref "PCIE-NORTH") (pin "B14") (pinfunction "VCCIO_B14") (pintype "passive"))
    )
    (net (code "69") (name "unconnected-(PCIE-SOUTH-5V-PadB12)") (class "Default")
      (node (ref "PCIE-SOUTH") (pin "B12") (pinfunction "5V_B12") (pintype "passive"))
    )
    (net (code "70") (name "unconnected-(PCIE-SOUTH-PWRGD-PadA11)") (class "Default")
      (node (ref "PCIE-SOUTH") (pin "A11") (pinfunction "PWRGD_A11") (pintype "passive"))
    )
    (net (code "71") (name "unconnected-(PCIE-SOUTH-SCL-PadB2)") (class "Default")
      (node (ref "PCIE-SOUTH") (pin "B2") (pinfunction "SCL_B2") (pintype "passive"))
    )
    (net (code "72") (name "unconnected-(PCIE-SOUTH-SDA-PadB1)") (class "Default")
      (node (ref "PCIE-SOUTH") (pin "B1") (pinfunction "SDA_B1") (pintype "passive"))
    )
    (net (code "73") (name "unconnected-(PCIE-SOUTH-VCCIO-PadB14)") (class "Default")
      (node (ref "PCIE-SOUTH") (pin "B14") (pinfunction "VCCIO_B14") (pintype "passive"))
    )
    (net (code "74") (name "unconnected-(PCIE-SOUTH-V_I2C-PadB3)") (class "Default")
      (node (ref "PCIE-SOUTH") (pin "B3") (pinfunction "V_I2C_B3") (pintype "passive"))
    )
  )
)
